# Adafruit_Hallowing_M4.net
KiCad netlist of a schematic drawn in EAGLE
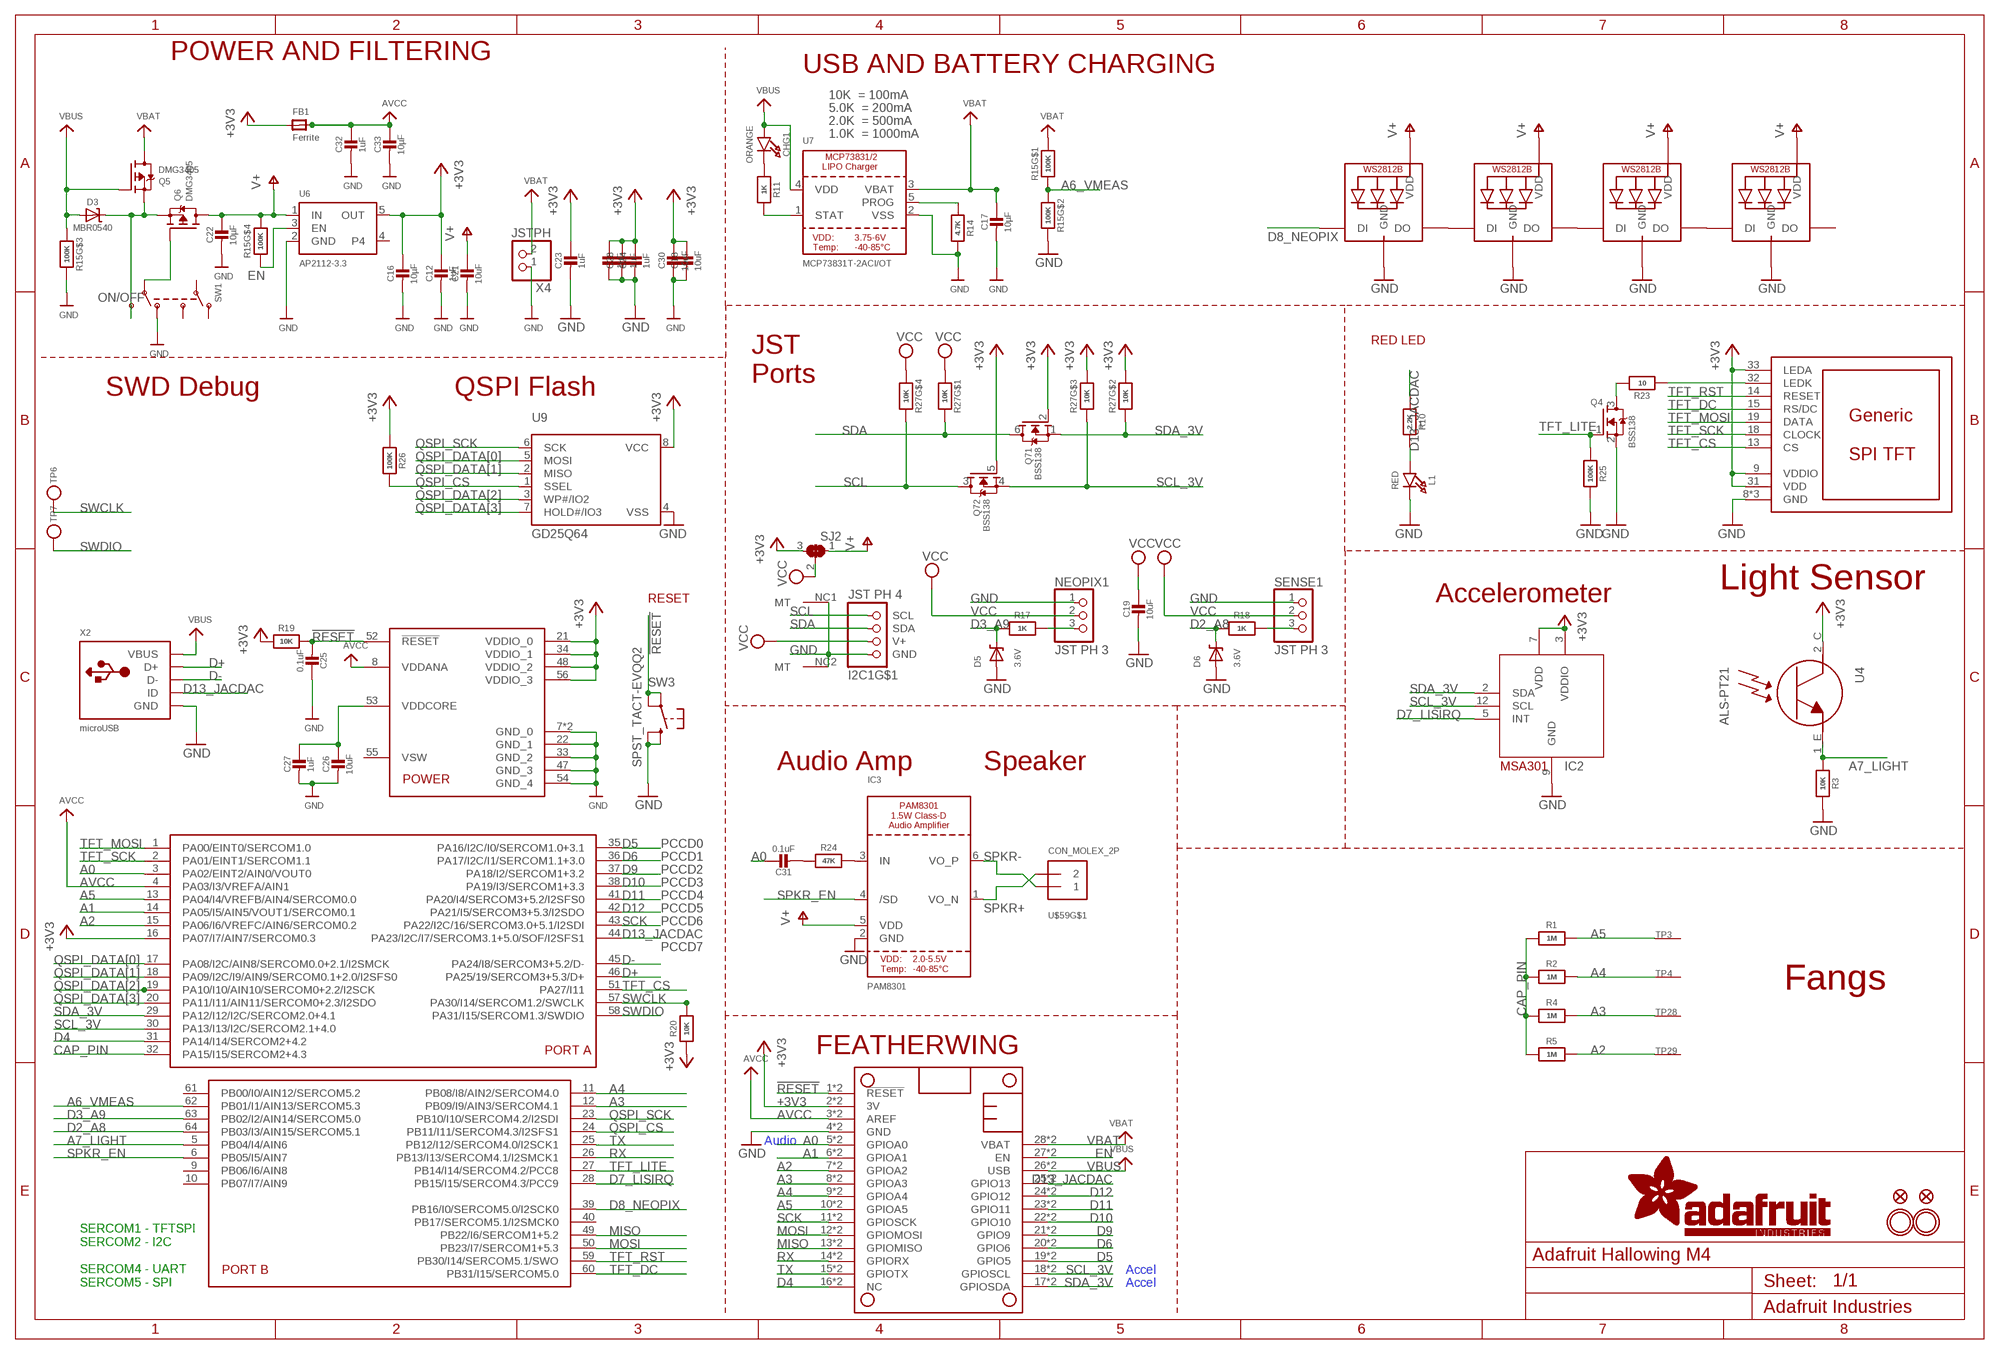
[diagram p0: schematic, sheet 1]

(export (version "E")
  (design (tool "Eeschema 10.0.6"))
  (components
    (comp (ref "C12")
      (value "1uF")
      (footprint "eagle-import:0603-NO")
      (libsource (lib "eagle-import") (part "CAP_CERAMIC0603_NO"))
    )
    (comp (ref "C16")
      (value "10µF")
      (footprint "eagle-import:0805-NO")
      (fields (field (name "REV") "C"))
      (libsource (lib "eagle-import") (part "CAP_CERAMIC0805-NOOUTLINE"))
    )
    (comp (ref "C17")
      (value "10µF")
      (footprint "eagle-import:0805-NO")
      (libsource (lib "eagle-import") (part "CAP_CERAMIC0805-NOOUTLINE"))
    )
    (comp (ref "C18")
      (value "10uF")
      (footprint "eagle-import:0805-NO")
      (libsource (lib "eagle-import") (part "CAP_CERAMIC0805-NOOUTLINE"))
    )
    (comp (ref "C19")
      (value "10uF")
      (footprint "eagle-import:0805-NO")
      (libsource (lib "eagle-import") (part "CAP_CERAMIC0805-NOOUTLINE"))
    )
    (comp (ref "C21")
      (value "10uF")
      (footprint "eagle-import:0805-NO")
      (libsource (lib "eagle-import") (part "CAP_CERAMIC0805-NOOUTLINE"))
    )
    (comp (ref "C22")
      (value "10µF")
      (footprint "eagle-import:0805-NO")
      (libsource (lib "eagle-import") (part "CAP_CERAMIC0805-NOOUTLINE"))
    )
    (comp (ref "C23")
      (value "1uF")
      (footprint "eagle-import:0603-NO")
      (libsource (lib "eagle-import") (part "CAP_CERAMIC0603_NO"))
    )
    (comp (ref "C24")
      (value "1uF")
      (footprint "eagle-import:0603-NO")
      (libsource (lib "eagle-import") (part "CAP_CERAMIC0603_NO"))
    )
    (comp (ref "C25")
      (value "0.1uF")
      (footprint "eagle-import:0603-NO")
      (libsource (lib "eagle-import") (part "CAP_CERAMIC0603_NO"))
    )
    (comp (ref "C26")
      (value "10uF")
      (footprint "eagle-import:0805-NO")
      (libsource (lib "eagle-import") (part "CAP_CERAMIC0805-NOOUTLINE"))
    )
    (comp (ref "C27")
      (value "1uF")
      (footprint "eagle-import:0603-NO")
      (libsource (lib "eagle-import") (part "CAP_CERAMIC0603_NO"))
    )
    (comp (ref "C28")
      (value "1uF")
      (footprint "eagle-import:0603-NO")
      (libsource (lib "eagle-import") (part "CAP_CERAMIC0603_NO"))
    )
    (comp (ref "C29")
      (value "1uF")
      (footprint "eagle-import:0603-NO")
      (libsource (lib "eagle-import") (part "CAP_CERAMIC0603_NO"))
    )
    (comp (ref "C30")
      (value "10uF")
      (footprint "eagle-import:0805-NO")
      (libsource (lib "eagle-import") (part "CAP_CERAMIC0805-NOOUTLINE"))
    )
    (comp (ref "C31")
      (value "0.1uF")
      (footprint "eagle-import:0603-NO")
      (libsource (lib "eagle-import") (part "CAP_CERAMIC0603_NO"))
    )
    (comp (ref "C32")
      (value "1uF")
      (footprint "eagle-import:0603-NO")
      (libsource (lib "eagle-import") (part "CAP_CERAMIC0603_NO"))
    )
    (comp (ref "C33")
      (value "10µF")
      (footprint "eagle-import:0805-NO")
      (libsource (lib "eagle-import") (part "CAP_CERAMIC0805-NOOUTLINE"))
    )
    (comp (ref "CHG1")
      (value "ORANGE")
      (footprint "eagle-import:CHIPLED_0805_NOOUTLINE")
      (libsource (lib "eagle-import") (part "LED0805_NOOUTLINE"))
    )
    (comp (ref "D3")
      (value "MBR0540")
      (footprint "eagle-import:SOD-123")
      (libsource (lib "eagle-import") (part "DIODE-SCHOTTKYSOD-123"))
    )
    (comp (ref "D5")
      (value "3.6V")
      (footprint "eagle-import:SOD-323")
      (libsource (lib "eagle-import") (part "DIODE-ZENERSOD323"))
    )
    (comp (ref "D6")
      (value "3.6V")
      (footprint "eagle-import:SOD-323")
      (libsource (lib "eagle-import") (part "DIODE-ZENERSOD323"))
    )
    (comp (ref "FB1")
      (value "Ferrite")
      (footprint "eagle-import:0805-NO")
      (libsource (lib "eagle-import") (part "FERRITE-0805NO"))
    )
    (comp (ref "I2C1")
      (value "JST PH 4")
      (footprint "eagle-import:JSTPH4")
      (libsource (lib "eagle-import") (part "STEMMA_I2C_RASMT"))
    )
    (comp (ref "IC2")
      (value "MSA301")
      (footprint "eagle-import:LGA12_2X2MM")
      (libsource (lib "eagle-import") (part "MSA301"))
    )
    (comp (ref "IC3")
      (value "PAM8301")
      (footprint "eagle-import:SOT23-6")
      (libsource (lib "eagle-import") (part "PAM8301"))
    )
    (comp (ref "L1")
      (value "RED")
      (footprint "eagle-import:CHIPLED_0805_NOOUTLINE")
      (libsource (lib "eagle-import") (part "LED0805_NOOUTLINE"))
    )
    (comp (ref "LED1")
      (value "WS2812B_4020")
      (footprint "eagle-import:WS2812B_4020")
      (libsource (lib "eagle-import") (part "WS2812B_4020"))
    )
    (comp (ref "LED2")
      (value "WS2812B_4020")
      (footprint "eagle-import:WS2812B_4020")
      (libsource (lib "eagle-import") (part "WS2812B_4020"))
    )
    (comp (ref "LED3")
      (value "WS2812B_4020")
      (footprint "eagle-import:WS2812B_4020")
      (libsource (lib "eagle-import") (part "WS2812B_4020"))
    )
    (comp (ref "LED4")
      (value "WS2812B_4020")
      (footprint "eagle-import:WS2812B_4020")
      (libsource (lib "eagle-import") (part "WS2812B_4020"))
    )
    (comp (ref "MS2")
      (value "FEATHERWING_SMTDUALNOHOLES")
      (footprint "eagle-import:FEATHERWING_SMT_NOHOLES")
      (libsource (lib "eagle-import") (part "FEATHERWING_SMTDUALNOHOLES"))
    )
    (comp (ref "NEOPIX1")
      (value "JST PH 3")
      (footprint "eagle-import:JSTPH3")
      (libsource (lib "eagle-import") (part "CON_JST_PH_3PIN"))
    )
    (comp (ref "Q4")
      (value "BSS138")
      (footprint "eagle-import:SOT23-WIDE")
      (libsource (lib "eagle-import") (part "MOSFET-NWIDE"))
    )
    (comp (ref "Q5")
      (value "DMG3405")
      (footprint "eagle-import:SOT23-R")
      (libsource (lib "eagle-import") (part "MOSFET-P"))
    )
    (comp (ref "Q6")
      (value "DMG3405")
      (footprint "eagle-import:SOT23-R")
      (libsource (lib "eagle-import") (part "MOSFET-P"))
    )
    (comp (ref "Q7")
      (value "BSS138")
      (footprint "eagle-import:SOT363")
      (libsource (lib "eagle-import") (part "MOSFET-N_DUAL"))
    )
    (comp (ref "R1")
      (value "1M")
      (footprint "eagle-import:0603-NO")
      (libsource (lib "eagle-import") (part "RESISTOR_0603_NOOUT"))
    )
    (comp (ref "R2")
      (value "1M")
      (footprint "eagle-import:0603-NO")
      (libsource (lib "eagle-import") (part "RESISTOR_0603_NOOUT"))
    )
    (comp (ref "R3")
      (value "10K")
      (footprint "eagle-import:0603-NO")
      (libsource (lib "eagle-import") (part "RESISTOR_0603_NOOUT"))
    )
    (comp (ref "R4")
      (value "1M")
      (footprint "eagle-import:0603-NO")
      (libsource (lib "eagle-import") (part "RESISTOR_0603_NOOUT"))
    )
    (comp (ref "R5")
      (value "1M")
      (footprint "eagle-import:0603-NO")
      (libsource (lib "eagle-import") (part "RESISTOR_0603_NOOUT"))
    )
    (comp (ref "R10")
      (value "2.2K")
      (footprint "eagle-import:0603-NO")
      (libsource (lib "eagle-import") (part "RESISTOR_0603_NOOUT"))
    )
    (comp (ref "R11")
      (value "1K")
      (footprint "eagle-import:0603-NO")
      (libsource (lib "eagle-import") (part "RESISTOR_0603_NOOUT"))
    )
    (comp (ref "R14")
      (value "4.7K")
      (footprint "eagle-import:0603-NO")
      (libsource (lib "eagle-import") (part "RESISTOR_0603_NOOUT"))
    )
    (comp (ref "R15")
      (value "100K")
      (footprint "eagle-import:RESPACK_4X0603")
      (libsource (lib "eagle-import") (part "RESISTOR_4PACK"))
    )
    (comp (ref "R17")
      (value "1K")
      (footprint "eagle-import:0603-NO")
      (libsource (lib "eagle-import") (part "RESISTOR_0603_NOOUT"))
    )
    (comp (ref "R18")
      (value "1K")
      (footprint "eagle-import:0603-NO")
      (libsource (lib "eagle-import") (part "RESISTOR_0603_NOOUT"))
    )
    (comp (ref "R19")
      (value "10K")
      (footprint "eagle-import:0603-NO")
      (libsource (lib "eagle-import") (part "RESISTOR_0603_NOOUT"))
    )
    (comp (ref "R20")
      (value "10K")
      (footprint "eagle-import:0603-NO")
      (libsource (lib "eagle-import") (part "RESISTOR_0603_NOOUT"))
    )
    (comp (ref "R23")
      (value "10")
      (footprint "eagle-import:0603-NO")
      (libsource (lib "eagle-import") (part "RESISTOR_0603_NOOUT"))
    )
    (comp (ref "R24")
      (value "47K")
      (footprint "eagle-import:0603-NO")
      (libsource (lib "eagle-import") (part "RESISTOR_0603_NOOUT"))
    )
    (comp (ref "R25")
      (value "100K")
      (footprint "eagle-import:0603-NO")
      (libsource (lib "eagle-import") (part "RESISTOR_0603_NOOUT"))
    )
    (comp (ref "R26")
      (value "100K")
      (footprint "eagle-import:0603-NO")
      (libsource (lib "eagle-import") (part "RESISTOR_0603_NOOUT"))
    )
    (comp (ref "R27")
      (value "10K")
      (footprint "eagle-import:RESPACK_4X0603")
      (libsource (lib "eagle-import") (part "RESISTOR_4PACK"))
    )
    (comp (ref "SENSE1")
      (value "JST PH 3")
      (footprint "eagle-import:JSTPH3")
      (libsource (lib "eagle-import") (part "CON_JST_PH_3PIN"))
    )
    (comp (ref "SJ2")
      (value "SOLDERJUMPER_2WAY")
      (footprint "eagle-import:SOLDERJUMPER_2WAY_OPEN_NOPASTE")
      (libsource (lib "eagle-import") (part "SOLDERJUMPER_2WAY"))
    )
    (comp (ref "SW1")
      (value "SWITCH_DPDTEG1390")
      (footprint "eagle-import:EG1390")
      (libsource (lib "eagle-import") (part "SWITCH_DPDTEG1390"))
    )
    (comp (ref "SW3")
      (value "SPST_TACT-EVQQ2")
      (footprint "eagle-import:BTN_KMR2_4.6X2.8")
      (libsource (lib "eagle-import") (part "SWITCH_TACT_SMT4.6X2.8"))
    )
    (comp (ref "TFT1")
      (value "DISP_LCD_GENERIC_SPITFT_VDDIO_1.54_240X240_HANDSOLDER")
      (footprint "eagle-import:TFT_1.54IN_240X240_HANDSOLDER")
      (libsource (lib "eagle-import") (part "DISP_LCD_GENERIC_SPITFT_VDDIO_1.54_240X240_HANDSOLDER"))
    )
    (comp (ref "TP3")
      (value "SEWTAP_ALLILONG")
      (footprint "eagle-import:PCB_ALLI_LONG")
      (libsource (lib "eagle-import") (part "SEWTAP_ALLILONG"))
    )
    (comp (ref "TP4")
      (value "SEWTAPPCB_ALLIGATOR")
      (footprint "eagle-import:PCB_ALLI")
      (libsource (lib "eagle-import") (part "SEWTAPPCB_ALLIGATOR"))
    )
    (comp (ref "TP6")
      (value "TESTPOINTROUND1.5MM")
      (footprint "eagle-import:TESTPOINT_ROUND_1.5MM")
      (libsource (lib "eagle-import") (part "TESTPOINTROUND1.5MM"))
    )
    (comp (ref "TP7")
      (value "TESTPOINTROUND1.5MM")
      (footprint "eagle-import:TESTPOINT_ROUND_1.5MM")
      (libsource (lib "eagle-import") (part "TESTPOINTROUND1.5MM"))
    )
    (comp (ref "TP28")
      (value "SEWTAPPCB_ALLIGATOR")
      (footprint "eagle-import:PCB_ALLI")
      (libsource (lib "eagle-import") (part "SEWTAPPCB_ALLIGATOR"))
    )
    (comp (ref "TP29")
      (value "SEWTAP_ALLILONG")
      (footprint "eagle-import:PCB_ALLI_LONG")
      (libsource (lib "eagle-import") (part "SEWTAP_ALLILONG"))
    )
    (comp (ref "U$31")
      (value "MOUNTINGHOLE2.5")
      (footprint "eagle-import:MOUNTINGHOLE_2.5_PLATED")
      (libsource (lib "eagle-import") (part "MOUNTINGHOLE2.5"))
    )
    (comp (ref "U$32")
      (value "MOUNTINGHOLE2.5")
      (footprint "eagle-import:MOUNTINGHOLE_2.5_PLATED")
      (libsource (lib "eagle-import") (part "MOUNTINGHOLE2.5"))
    )
    (comp (ref "U$34")
      (value "FIDUCIAL_1MM")
      (footprint "eagle-import:FIDUCIAL_1MM")
      (libsource (lib "eagle-import") (part "FIDUCIAL_1MM"))
    )
    (comp (ref "U$35")
      (value "FIDUCIAL_1MM")
      (footprint "eagle-import:FIDUCIAL_1MM")
      (libsource (lib "eagle-import") (part "FIDUCIAL_1MM"))
    )
    (comp (ref "U$59")
      (value "CON_MOLEX_2P")
      (footprint "eagle-import:53398-0271")
      (libsource (lib "eagle-import") (part "CON_MOLEX_2P"))
    )
    (comp (ref "U$63")
      (value "ATSAMD51J19")
      (footprint "eagle-import:PQFN64-1")
      (libsource (lib "eagle-import") (part "ATSAMD51J"))
    )
    (comp (ref "U4")
      (value "ALS-PT21")
      (footprint "eagle-import:ALS-PT26-21C")
      (libsource (lib "eagle-import") (part "PHOTOTRANSISTOR_PT26-21C"))
    )
    (comp (ref "U6")
      (value "AP2112-3.3")
      (footprint "eagle-import:SOT23-5")
      (libsource (lib "eagle-import") (part "VREG_SOT23-5"))
    )
    (comp (ref "U7")
      (value "MCP73831T-2ACI/OT")
      (footprint "eagle-import:SOT23-5")
      (libsource (lib "eagle-import") (part "MCP73831/2"))
    )
    (comp (ref "U9")
      (value "GD25Q64")
      (footprint "eagle-import:SOIC8_208MIL")
      (libsource (lib "eagle-import") (part "SPIFLASH_8PIN208MIL"))
    )
    (comp (ref "X2")
      (value "microUSB")
      (footprint "eagle-import:4UCONN_20329_V2")
      (libsource (lib "eagle-import") (part "USB_MICRO_20329_V2"))
    )
    (comp (ref "X4")
      (value "JSTPH")
      (footprint "eagle-import:JSTPH2")
      (libsource (lib "eagle-import") (part "CON_JST_PH_2PIN"))
    )
  )
  (nets
    (net (code "1") (name "+3V3") (class "Default")
      (node (ref "C12") (pin "1") (pinfunction "1_1") (pintype "passive"))
      (node (ref "C16") (pin "1") (pinfunction "1_1") (pintype "passive"))
      (node (ref "C18") (pin "1") (pinfunction "1_1") (pintype "passive"))
      (node (ref "C23") (pin "1") (pinfunction "1_1") (pintype "passive"))
      (node (ref "C24") (pin "1") (pinfunction "1_1") (pintype "passive"))
      (node (ref "C28") (pin "1") (pinfunction "1_1") (pintype "passive"))
      (node (ref "C29") (pin "1") (pinfunction "1_1") (pintype "passive"))
      (node (ref "C30") (pin "1") (pinfunction "1_1") (pintype "passive"))
      (node (ref "FB1") (pin "1") (pinfunction "P$1_1") (pintype "passive"))
      (node (ref "IC2") (pin "3") (pinfunction "VDDIO_3") (pintype "power_in"))
      (node (ref "IC2") (pin "7") (pinfunction "VDD_7") (pintype "power_in"))
      (node (ref "MS2") (pin "2") (pinfunction "3V_2") (pintype "power_in"))
      (node (ref "MS2") (pin "2B") (pinfunction "3V_2B") (pintype "power_in"))
      (node (ref "Q7") (pin "2") (pinfunction "G_2") (pintype "bidirectional"))
      (node (ref "Q7") (pin "5") (pinfunction "G_5") (pintype "bidirectional"))
      (node (ref "R19") (pin "1") (pinfunction "1_1") (pintype "passive"))
      (node (ref "R20") (pin "1") (pinfunction "1_1") (pintype "passive"))
      (node (ref "R26") (pin "1") (pinfunction "1_1") (pintype "passive"))
      (node (ref "R27") (pin "2") (pinfunction "1_2") (pintype "passive"))
      (node (ref "R27") (pin "3") (pinfunction "1_3") (pintype "passive"))
      (node (ref "SJ2") (pin "3") (pinfunction "3_3") (pintype "passive"))
      (node (ref "TFT1") (pin "31") (pinfunction "VDD_31") (pintype "power_in"))
      (node (ref "TFT1") (pin "33") (pinfunction "LEDA_33") (pintype "input"))
      (node (ref "TFT1") (pin "9") (pinfunction "VDDIO_9") (pintype "power_in"))
      (node (ref "U$63") (pin "16") (pinfunction "PA07/I7/AIN7/SERCOM0.3_16") (pintype "bidirectional"))
      (node (ref "U$63") (pin "21") (pinfunction "VDDIO_0_21") (pintype "bidirectional"))
      (node (ref "U$63") (pin "34") (pinfunction "VDDIO_1_34") (pintype "bidirectional"))
      (node (ref "U$63") (pin "48") (pinfunction "VDDIO_2_48") (pintype "bidirectional"))
      (node (ref "U$63") (pin "56") (pinfunction "VDDIO_3_56") (pintype "bidirectional"))
      (node (ref "U4") (pin "2_C") (pinfunction "C_2_C") (pintype "bidirectional"))
      (node (ref "U6") (pin "5") (pinfunction "OUT_5") (pintype "power_in"))
      (node (ref "U9") (pin "8") (pinfunction "VCC_8") (pintype "bidirectional"))
    )
    (net (code "2") (name "/A0") (class "Default")
      (node (ref "C31") (pin "1") (pinfunction "1_1") (pintype "passive"))
      (node (ref "MS2") (pin "5") (pinfunction "GPIOA0_5") (pintype "bidirectional"))
      (node (ref "MS2") (pin "5B") (pinfunction "GPIOA0_5B") (pintype "bidirectional"))
      (node (ref "U$63") (pin "3") (pinfunction "PA02/EINT2/AIN0/VOUT0_3") (pintype "bidirectional"))
    )
    (net (code "3") (name "/A1") (class "Default")
      (node (ref "MS2") (pin "6") (pinfunction "GPIOA1_6") (pintype "bidirectional"))
      (node (ref "MS2") (pin "6B") (pinfunction "GPIOA1_6B") (pintype "bidirectional"))
      (node (ref "U$63") (pin "14") (pinfunction "PA05/I5/AIN5/VOUT1/SERCOM0.1_14") (pintype "bidirectional"))
    )
    (net (code "4") (name "/A2") (class "Default")
      (node (ref "MS2") (pin "7") (pinfunction "GPIOA2_7") (pintype "bidirectional"))
      (node (ref "MS2") (pin "7B") (pinfunction "GPIOA2_7B") (pintype "bidirectional"))
      (node (ref "R5") (pin "1") (pinfunction "1_1") (pintype "passive"))
      (node (ref "TP29") (pin "P$1") (pinfunction "SEW_P$1") (pintype "bidirectional"))
      (node (ref "U$63") (pin "15") (pinfunction "PA06/I6/VREFC/AIN6/SERCOM0.2_15") (pintype "bidirectional"))
    )
    (net (code "5") (name "/A3") (class "Default")
      (node (ref "MS2") (pin "8") (pinfunction "GPIOA3_8") (pintype "bidirectional"))
      (node (ref "MS2") (pin "8B") (pinfunction "GPIOA3_8B") (pintype "bidirectional"))
      (node (ref "R4") (pin "1") (pinfunction "1_1") (pintype "passive"))
      (node (ref "TP28") (pin "P$1") (pinfunction "SEW_P$1") (pintype "bidirectional"))
      (node (ref "U$63") (pin "12") (pinfunction "PB09/I9/AIN3/SERCOM4.1_12") (pintype "bidirectional"))
    )
    (net (code "6") (name "/A4") (class "Default")
      (node (ref "MS2") (pin "9") (pinfunction "GPIOA4_9") (pintype "bidirectional"))
      (node (ref "MS2") (pin "9B") (pinfunction "GPIOA4_9B") (pintype "bidirectional"))
      (node (ref "R2") (pin "1") (pinfunction "1_1") (pintype "passive"))
      (node (ref "TP4") (pin "P$1") (pinfunction "SEW_P$1") (pintype "bidirectional"))
      (node (ref "U$63") (pin "11") (pinfunction "PB08/I8/AIN2/SERCOM4.0_11") (pintype "bidirectional"))
    )
    (net (code "7") (name "/A5") (class "Default")
      (node (ref "MS2") (pin "10") (pinfunction "GPIOA5_10") (pintype "bidirectional"))
      (node (ref "MS2") (pin "10B") (pinfunction "GPIOA5_10B") (pintype "bidirectional"))
      (node (ref "R1") (pin "1") (pinfunction "1_1") (pintype "passive"))
      (node (ref "TP3") (pin "P$1") (pinfunction "SEW_P$1") (pintype "bidirectional"))
      (node (ref "U$63") (pin "13") (pinfunction "PA04/I4/VREFB/AIN4/SERCOM0.0_13") (pintype "bidirectional"))
    )
    (net (code "8") (name "/A6_VMEAS") (class "Default")
      (node (ref "R15") (pin "1") (pinfunction "1_1") (pintype "passive"))
      (node (ref "R15") (pin "2") (pinfunction "1_2") (pintype "passive"))
      (node (ref "U$63") (pin "62") (pinfunction "PB01/I1/AIN13/SERCOM5.3_62") (pintype "bidirectional"))
    )
    (net (code "9") (name "/A7_LIGHT") (class "Default")
      (node (ref "R3") (pin "2") (pinfunction "2_2") (pintype "passive"))
      (node (ref "U$63") (pin "5") (pinfunction "PB04/I4/AIN6_5") (pintype "bidirectional"))
      (node (ref "U4") (pin "1_E") (pinfunction "E_1_E") (pintype "bidirectional"))
    )
    (net (code "10") (name "/CAP_PIN") (class "Default")
      (node (ref "R1") (pin "2") (pinfunction "2_2") (pintype "passive"))
      (node (ref "R2") (pin "2") (pinfunction "2_2") (pintype "passive"))
      (node (ref "R4") (pin "2") (pinfunction "2_2") (pintype "passive"))
      (node (ref "R5") (pin "2") (pinfunction "2_2") (pintype "passive"))
      (node (ref "U$63") (pin "32") (pinfunction "PA15/I15/SERCOM2+4.3_32") (pintype "bidirectional"))
    )
    (net (code "11") (name "/D+") (class "Default")
      (node (ref "U$63") (pin "46") (pinfunction "PA25/19/SERCOM3+5.3/D+_46") (pintype "bidirectional"))
      (node (ref "X2") (pin "D+") (pinfunction "D+_D+") (pintype "bidirectional"))
    )
    (net (code "12") (name "/D-") (class "Default")
      (node (ref "U$63") (pin "45") (pinfunction "PA24/I8/SERCOM3+5.2/D-_45") (pintype "bidirectional"))
      (node (ref "X2") (pin "D-") (pinfunction "D-_D-") (pintype "bidirectional"))
    )
    (net (code "13") (name "/D2_A8") (class "Default")
      (node (ref "D6") (pin "C") (pinfunction "C_C") (pintype "passive"))
      (node (ref "R18") (pin "2") (pinfunction "2_2") (pintype "passive"))
      (node (ref "U$63") (pin "64") (pinfunction "PB03/I3/AIN15/SERCOM5.1_64") (pintype "bidirectional"))
    )
    (net (code "14") (name "/D3_A9") (class "Default")
      (node (ref "D5") (pin "C") (pinfunction "C_C") (pintype "passive"))
      (node (ref "R17") (pin "2") (pinfunction "2_2") (pintype "passive"))
      (node (ref "U$63") (pin "63") (pinfunction "PB02/I2/AIN14/SERCOM5.0_63") (pintype "bidirectional"))
    )
    (net (code "15") (name "/D4") (class "Default")
      (node (ref "MS2") (pin "16") (pinfunction "NC_16") (pintype "passive"))
      (node (ref "MS2") (pin "16B") (pinfunction "NC_16B") (pintype "passive"))
      (node (ref "U$63") (pin "31") (pinfunction "PA14/I14/SERCOM2+4.2_31") (pintype "bidirectional"))
    )
    (net (code "16") (name "/D5") (class "Default")
      (node (ref "MS2") (pin "19") (pinfunction "GPIO5_19") (pintype "bidirectional"))
      (node (ref "MS2") (pin "19B") (pinfunction "GPIO5_19B") (pintype "bidirectional"))
      (node (ref "U$63") (pin "35") (pinfunction "PA16/I2C/I0/SERCOM1.0+3.1_35") (pintype "bidirectional"))
    )
    (net (code "17") (name "/D6") (class "Default")
      (node (ref "MS2") (pin "20") (pinfunction "GPIO6_20") (pintype "bidirectional"))
      (node (ref "MS2") (pin "20B") (pinfunction "GPIO6_20B") (pintype "bidirectional"))
      (node (ref "U$63") (pin "36") (pinfunction "PA17/I2C/I1/SERCOM1.1+3.0_36") (pintype "bidirectional"))
    )
    (net (code "18") (name "/D7_LISIRQ") (class "Default")
      (node (ref "IC2") (pin "5") (pinfunction "INT_5") (pintype "output"))
      (node (ref "U$63") (pin "28") (pinfunction "PB15/I15/SERCOM4.3/PCC9_28") (pintype "bidirectional"))
    )
    (net (code "19") (name "/D8_NEOPIX") (class "Default")
      (node (ref "LED2") (pin "1") (pinfunction "DI_1") (pintype "input"))
      (node (ref "U$63") (pin "39") (pinfunction "PB16/I0/SERCOM5.0/I2SCK0_39") (pintype "bidirectional"))
    )
    (net (code "20") (name "/D9") (class "Default")
      (node (ref "MS2") (pin "21") (pinfunction "GPIO9_21") (pintype "bidirectional"))
      (node (ref "MS2") (pin "21B") (pinfunction "GPIO9_21B") (pintype "bidirectional"))
      (node (ref "U$63") (pin "37") (pinfunction "PA18/I2/SERCOM1+3.2_37") (pintype "bidirectional"))
    )
    (net (code "21") (name "/D10") (class "Default")
      (node (ref "MS2") (pin "22") (pinfunction "GPIO10_22") (pintype "bidirectional"))
      (node (ref "MS2") (pin "22B") (pinfunction "GPIO10_22B") (pintype "bidirectional"))
      (node (ref "U$63") (pin "38") (pinfunction "PA19/I3/SERCOM1+3.3_38") (pintype "bidirectional"))
    )
    (net (code "22") (name "/D11") (class "Default")
      (node (ref "MS2") (pin "23") (pinfunction "GPIO11_23") (pintype "bidirectional"))
      (node (ref "MS2") (pin "23B") (pinfunction "GPIO11_23B") (pintype "bidirectional"))
      (node (ref "U$63") (pin "41") (pinfunction "PA20/I4/SERCOM3+5.2/I2SFS0_41") (pintype "bidirectional"))
    )
    (net (code "23") (name "/D12") (class "Default")
      (node (ref "MS2") (pin "24") (pinfunction "GPIO12_24") (pintype "bidirectional"))
      (node (ref "MS2") (pin "24B") (pinfunction "GPIO12_24B") (pintype "bidirectional"))
      (node (ref "U$63") (pin "42") (pinfunction "PA21/I5/SERCOM3+5.3/I2SDO_42") (pintype "bidirectional"))
    )
    (net (code "24") (name "/D13_JACDAC") (class "Default")
      (node (ref "MS2") (pin "25") (pinfunction "GPIO13_25") (pintype "bidirectional"))
      (node (ref "MS2") (pin "25B") (pinfunction "GPIO13_25B") (pintype "bidirectional"))
      (node (ref "R10") (pin "1") (pinfunction "1_1") (pintype "passive"))
      (node (ref "U$63") (pin "44") (pinfunction "PA23/I2C/I7/SERCOM3.1+5.0/SOF/I2SFS1_44") (pintype "bidirectional"))
      (node (ref "X2") (pin "ID") (pinfunction "ID_ID") (pintype "bidirectional"))
    )
    (net (code "25") (name "/EN") (class "Default")
      (node (ref "MS2") (pin "27") (pinfunction "EN_27") (pintype "passive"))
      (node (ref "MS2") (pin "27B") (pinfunction "EN_27B") (pintype "passive"))
      (node (ref "R15") (pin "4") (pinfunction "1_4") (pintype "passive"))
      (node (ref "U6") (pin "3") (pinfunction "EN_3") (pintype "input"))
    )
    (net (code "26") (name "/MISO") (class "Default")
      (node (ref "MS2") (pin "13") (pinfunction "GPIOMISO_13") (pintype "bidirectional"))
      (node (ref "MS2") (pin "13B") (pinfunction "GPIOMISO_13B") (pintype "bidirectional"))
      (node (ref "U$63") (pin "49") (pinfunction "PB22/I6/SERCOM1+5.2_49") (pintype "bidirectional"))
    )
    (net (code "27") (name "/MOSI") (class "Default")
      (node (ref "MS2") (pin "12") (pinfunction "GPIOMOSI_12") (pintype "bidirectional"))
      (node (ref "MS2") (pin "12B") (pinfunction "GPIOMOSI_12B") (pintype "bidirectional"))
      (node (ref "U$63") (pin "50") (pinfunction "PB23/I7/SERCOM1+5.3_50") (pintype "bidirectional"))
    )
    (net (code "28") (name "/ON{slash}OFF") (class "Default")
      (node (ref "Q6") (pin "1") (pinfunction "G_1") (pintype "passive"))
      (node (ref "SW1") (pin "P2") (pinfunction "P2_P2") (pintype "passive"))
    )
    (net (code "29") (name "/QSPI_CS") (class "Default")
      (node (ref "R26") (pin "2") (pinfunction "2_2") (pintype "passive"))
      (node (ref "U$63") (pin "24") (pinfunction "PB11/I11/SERCOM4.3/I2SFS1_24") (pintype "bidirectional"))
      (node (ref "U9") (pin "1") (pinfunction "SSEL_1") (pintype "bidirectional"))
    )
    (net (code "30") (name "/QSPI_DATA[0]") (class "Default")
      (node (ref "U$63") (pin "17") (pinfunction "PA08/I2C/AIN8/SERCOM0.0+2.1/I2SMCK_17") (pintype "bidirectional"))
      (node (ref "U9") (pin "5") (pinfunction "MOSI_5") (pintype "bidirectional"))
    )
    (net (code "31") (name "/QSPI_DATA[1]") (class "Default")
      (node (ref "U$63") (pin "18") (pinfunction "PA09/I2C/I9/AIN9/SERCOM0.1+2.0/I2SFS0_18") (pintype "bidirectional"))
      (node (ref "U9") (pin "2") (pinfunction "MISO_2") (pintype "bidirectional"))
    )
    (net (code "32") (name "/QSPI_DATA[2]") (class "Default")
      (node (ref "U$63") (pin "19") (pinfunction "PA10/I10/AIN10/SERCOM0+2.2/I2SCK_19") (pintype "bidirectional"))
      (node (ref "U9") (pin "3") (pinfunction "WP#/IO2_3") (pintype "bidirectional"))
    )
    (net (code "33") (name "/QSPI_DATA[3]") (class "Default")
      (node (ref "U$63") (pin "20") (pinfunction "PA11/I11/AIN11/SERCOM0+2.3/I2SDO_20") (pintype "bidirectional"))
      (node (ref "U9") (pin "7") (pinfunction "HOLD#/IO3_7") (pintype "bidirectional"))
    )
    (net (code "34") (name "/QSPI_SCK") (class "Default")
      (node (ref "U$63") (pin "23") (pinfunction "PB10/I10/SERCOM4.2/I2SDI_23") (pintype "bidirectional"))
      (node (ref "U9") (pin "6") (pinfunction "SCK_6") (pintype "bidirectional"))
    )
    (net (code "35") (name "/RX") (class "Default")
      (node (ref "MS2") (pin "14") (pinfunction "GPIORX_14") (pintype "bidirectional"))
      (node (ref "MS2") (pin "14B") (pinfunction "GPIORX_14B") (pintype "bidirectional"))
      (node (ref "U$63") (pin "26") (pinfunction "PB13/I13/SERCOM4.1/I2SMCK1_26") (pintype "bidirectional"))
    )
    (net (code "36") (name "/SCK") (class "Default")
      (node (ref "MS2") (pin "11") (pinfunction "GPIOSCK_11") (pintype "bidirectional"))
      (node (ref "MS2") (pin "11B") (pinfunction "GPIOSCK_11B") (pintype "bidirectional"))
      (node (ref "U$63") (pin "43") (pinfunction "PA22/I2C/16/SERCOM3.0+5.1/I2SDI_43") (pintype "bidirectional"))
    )
    (net (code "37") (name "/SCL") (class "Default")
      (node (ref "I2C1") (pin "4") (pinfunction "SCL_4") (pintype "passive"))
      (node (ref "Q7") (pin "3") (pinfunction "D_3") (pintype "bidirectional"))
      (node (ref "R27") (pin "5") (pinfunction "2_5") (pintype "passive"))
    )
    (net (code "38") (name "/SCL_3V") (class "Default")
      (node (ref "IC2") (pin "12") (pinfunction "SCL_12") (pintype "bidirectional"))
      (node (ref "MS2") (pin "18") (pinfunction "GPIOSCL_18") (pintype "bidirectional"))
      (node (ref "MS2") (pin "18B") (pinfunction "GPIOSCL_18B") (pintype "bidirectional"))
      (node (ref "Q7") (pin "4") (pinfunction "S_4") (pintype "bidirectional"))
      (node (ref "R27") (pin "6") (pinfunction "2_6") (pintype "passive"))
      (node (ref "U$63") (pin "30") (pinfunction "PA13/I13/I2C/SERCOM2.1+4.0_30") (pintype "bidirectional"))
    )
    (net (code "39") (name "/SDA") (class "Default")
      (node (ref "I2C1") (pin "3") (pinfunction "SDA_3") (pintype "passive"))
      (node (ref "Q7") (pin "6") (pinfunction "D_6") (pintype "bidirectional"))
      (node (ref "R27") (pin "8") (pinfunction "2_8") (pintype "passive"))
    )
    (net (code "40") (name "/SDA_3V") (class "Default")
      (node (ref "IC2") (pin "2") (pinfunction "SDA_2") (pintype "bidirectional"))
      (node (ref "MS2") (pin "17") (pinfunction "GPIOSDA_17") (pintype "bidirectional"))
      (node (ref "MS2") (pin "17B") (pinfunction "GPIOSDA_17B") (pintype "bidirectional"))
      (node (ref "Q7") (pin "1") (pinfunction "S_1") (pintype "bidirectional"))
      (node (ref "R27") (pin "7") (pinfunction "2_7") (pintype "passive"))
      (node (ref "U$63") (pin "29") (pinfunction "PA12/I12/I2C/SERCOM2.0+4.1_29") (pintype "bidirectional"))
    )
    (net (code "41") (name "/SPKR+") (class "Default")
      (node (ref "IC3") (pin "1") (pinfunction "VO_N_1") (pintype "output"))
      (node (ref "U$59") (pin "2") (pinfunction "2_2") (pintype "passive"))
    )
    (net (code "42") (name "/SPKR-") (class "Default")
      (node (ref "IC3") (pin "6") (pinfunction "VO_P_6") (pintype "output"))
      (node (ref "U$59") (pin "1") (pinfunction "1_1") (pintype "passive"))
    )
    (net (code "43") (name "/SPKR_EN") (class "Default")
      (node (ref "IC3") (pin "4") (pinfunction "/SD_4") (pintype "input"))
      (node (ref "U$63") (pin "6") (pinfunction "PB05/I5/AIN7_6") (pintype "bidirectional"))
    )
    (net (code "44") (name "/SWCLK") (class "Default")
      (node (ref "R20") (pin "2") (pinfunction "2_2") (pintype "passive"))
      (node (ref "TP6") (pin "P$1") (pinfunction "P$1_P$1") (pintype "bidirectional"))
      (node (ref "U$63") (pin "57") (pinfunction "PA30/I14/SERCOM1.2/SWCLK_57") (pintype "bidirectional"))
    )
    (net (code "45") (name "/SWDIO") (class "Default")
      (node (ref "TP7") (pin "P$1") (pinfunction "P$1_P$1") (pintype "bidirectional"))
      (node (ref "U$63") (pin "58") (pinfunction "PA31/I15/SERCOM1.3/SWDIO_58") (pintype "bidirectional"))
    )
    (net (code "46") (name "/TFT_CS") (class "Default")
      (node (ref "TFT1") (pin "13") (pinfunction "CS_13") (pintype "input"))
      (node (ref "U$63") (pin "51") (pinfunction "PA27/I11_51") (pintype "bidirectional"))
    )
    (net (code "47") (name "/TFT_DC") (class "Default")
      (node (ref "TFT1") (pin "15") (pinfunction "RS/DC_15") (pintype "input"))
      (node (ref "U$63") (pin "60") (pinfunction "PB31/I15/SERCOM5.0_60") (pintype "bidirectional"))
    )
    (net (code "48") (name "/TFT_LITE") (class "Default")
      (node (ref "Q4") (pin "1") (pinfunction "G_1") (pintype "bidirectional"))
      (node (ref "R25") (pin "1") (pinfunction "1_1") (pintype "passive"))
      (node (ref "U$63") (pin "27") (pinfunction "PB14/I14/SERCOM4.2/PCC8_27") (pintype "bidirectional"))
    )
    (net (code "49") (name "/TFT_MOSI") (class "Default")
      (node (ref "TFT1") (pin "19") (pinfunction "DATA_19") (pintype "bidirectional"))
      (node (ref "U$63") (pin "1") (pinfunction "PA00/EINT0/SERCOM1.0_1") (pintype "bidirectional"))
    )
    (net (code "50") (name "/TFT_RST") (class "Default")
      (node (ref "TFT1") (pin "14") (pinfunction "RESET_14") (pintype "input"))
      (node (ref "U$63") (pin "59") (pinfunction "PB30/I14/SERCOM5.1/SWO_59") (pintype "bidirectional"))
    )
    (net (code "51") (name "/TFT_SCK") (class "Default")
      (node (ref "TFT1") (pin "18") (pinfunction "CLOCK_18") (pintype "input"))
      (node (ref "U$63") (pin "2") (pinfunction "PA01/EINT1/SERCOM1.1_2") (pintype "bidirectional"))
    )
    (net (code "52") (name "/TX") (class "Default")
      (node (ref "MS2") (pin "15") (pinfunction "GPIOTX_15") (pintype "bidirectional"))
      (node (ref "MS2") (pin "15B") (pinfunction "GPIOTX_15B") (pintype "bidirectional"))
      (node (ref "U$63") (pin "25") (pinfunction "PB12/I12/SERCOM4.0/I2SCK1_25") (pintype "bidirectional"))
    )
    (net (code "53") (name "/~{RESET}") (class "Default")
      (node (ref "C25") (pin "2") (pinfunction "2_2") (pintype "passive"))
      (node (ref "MS2") (pin "1") (pinfunction "~{RESET}_1") (pintype "input"))
      (node (ref "MS2") (pin "1B") (pinfunction "~{RESET}_1B") (pintype "input"))
      (node (ref "R19") (pin "2") (pinfunction "2_2") (pintype "passive"))
      (node (ref "SW3") (pin "A") (pinfunction "P_A") (pintype "passive"))
      (node (ref "SW3") (pin "A'") (pinfunction "P1_A'") (pintype "passive"))
      (node (ref "U$63") (pin "52") (pinfunction "~{RESET}_52") (pintype "bidirectional"))
    )
    (net (code "54") (name "AVCC") (class "Default")
      (node (ref "C32") (pin "1") (pinfunction "1_1") (pintype "passive"))
      (node (ref "C33") (pin "1") (pinfunction "1_1") (pintype "passive"))
      (node (ref "FB1") (pin "2") (pinfunction "P$2_2") (pintype "passive"))
      (node (ref "MS2") (pin "3") (pinfunction "AREF_3") (pintype "passive"))
      (node (ref "MS2") (pin "3B") (pinfunction "AREF_3B") (pintype "passive"))
      (node (ref "U$63") (pin "4") (pinfunction "PA03/I3/VREFA/AIN1_4") (pintype "bidirectional"))
      (node (ref "U$63") (pin "8") (pinfunction "VDDANA_8") (pintype "bidirectional"))
    )
    (net (code "55") (name "GND") (class "Default")
      (node (ref "C12") (pin "2") (pinfunction "2_2") (pintype "passive"))
      (node (ref "C16") (pin "2") (pinfunction "2_2") (pintype "passive"))
      (node (ref "C17") (pin "2") (pinfunction "2_2") (pintype "passive"))
      (node (ref "C18") (pin "2") (pinfunction "2_2") (pintype "passive"))
      (node (ref "C19") (pin "2") (pinfunction "2_2") (pintype "passive"))
      (node (ref "C21") (pin "2") (pinfunction "2_2") (pintype "passive"))
      (node (ref "C22") (pin "2") (pinfunction "2_2") (pintype "passive"))
      (node (ref "C23") (pin "2") (pinfunction "2_2") (pintype "passive"))
      (node (ref "C24") (pin "2") (pinfunction "2_2") (pintype "passive"))
      (node (ref "C25") (pin "1") (pinfunction "1_1") (pintype "passive"))
      (node (ref "C26") (pin "2") (pinfunction "2_2") (pintype "passive"))
      (node (ref "C27") (pin "2") (pinfunction "2_2") (pintype "passive"))
      (node (ref "C28") (pin "2") (pinfunction "2_2") (pintype "passive"))
      (node (ref "C29") (pin "2") (pinfunction "2_2") (pintype "passive"))
      (node (ref "C30") (pin "2") (pinfunction "2_2") (pintype "passive"))
      (node (ref "C32") (pin "2") (pinfunction "2_2") (pintype "passive"))
      (node (ref "C33") (pin "2") (pinfunction "2_2") (pintype "passive"))
      (node (ref "D5") (pin "A") (pinfunction "A_A") (pintype "passive"))
      (node (ref "D6") (pin "A") (pinfunction "A_A") (pintype "passive"))
      (node (ref "I2C1") (pin "1") (pinfunction "GND_1") (pintype "passive"))
      (node (ref "I2C1") (pin "NC1") (pinfunction "MT_NC1") (pintype "bidirectional"))
      (node (ref "I2C1") (pin "NC2") (pinfunction "MT_NC2") (pintype "bidirectional"))
      (node (ref "IC2") (pin "9") (pinfunction "GND_9") (pintype "power_in"))
      (node (ref "IC3") (pin "2") (pinfunction "GND_2") (pintype "power_in"))
      (node (ref "L1") (pin "C") (pinfunction "C_C") (pintype "passive"))
      (node (ref "LED1") (pin "4") (pinfunction "GND_4") (pintype "power_in"))
      (node (ref "LED2") (pin "4") (pinfunction "GND_4") (pintype "power_in"))
      (node (ref "LED3") (pin "4") (pinfunction "GND_4") (pintype "power_in"))
      (node (ref "LED4") (pin "4") (pinfunction "GND_4") (pintype "power_in"))
      (node (ref "MS2") (pin "4") (pinfunction "GND_4") (pintype "power_in"))
      (node (ref "MS2") (pin "4B") (pinfunction "GND_4B") (pintype "power_in"))
      (node (ref "NEOPIX1") (pin "1") (pinfunction "1_1") (pintype "passive"))
      (node (ref "Q4") (pin "2") (pinfunction "S_2") (pintype "bidirectional"))
      (node (ref "R14") (pin "2") (pinfunction "2_2") (pintype "passive"))
      (node (ref "R15") (pin "6") (pinfunction "2_6") (pintype "passive"))
      (node (ref "R15") (pin "7") (pinfunction "2_7") (pintype "passive"))
      (node (ref "R25") (pin "2") (pinfunction "2_2") (pintype "passive"))
      (node (ref "R3") (pin "1") (pinfunction "1_1") (pintype "passive"))
      (node (ref "SENSE1") (pin "1") (pinfunction "1_1") (pintype "passive"))
      (node (ref "SW1") (pin "O2") (pinfunction "O2_O2") (pintype "passive"))
      (node (ref "SW3") (pin "B") (pinfunction "S_B") (pintype "passive"))
      (node (ref "SW3") (pin "B'") (pinfunction "S1_B'") (pintype "passive"))
      (node (ref "TFT1") (pin "21") (pinfunction "GND_21") (pintype "power_in"))
      (node (ref "TFT1") (pin "22") (pinfunction "GND_22") (pintype "power_in"))
      (node (ref "TFT1") (pin "8") (pinfunction "GND_8") (pintype "power_in"))
      (node (ref "U$63") (pin "22") (pinfunction "GND_1_22") (pintype "bidirectional"))
      (node (ref "U$63") (pin "33") (pinfunction "GND_2_33") (pintype "bidirectional"))
      (node (ref "U$63") (pin "47") (pinfunction "GND_3_47") (pintype "bidirectional"))
      (node (ref "U$63") (pin "54") (pinfunction "GND_4_54") (pintype "bidirectional"))
      (node (ref "U$63") (pin "7") (pinfunction "GND_0_7") (pintype "bidirectional"))
      (node (ref "U$63") (pin "EXP") (pinfunction "GND_0_EXP") (pintype "bidirectional"))
      (node (ref "U6") (pin "2") (pinfunction "GND_2") (pintype "power_in"))
      (node (ref "U7") (pin "2") (pinfunction "VSS_2") (pintype "power_in"))
      (node (ref "U9") (pin "4") (pinfunction "VSS_4") (pintype "bidirectional"))
      (node (ref "X2") (pin "BASE@1") (pinfunction "GND_BASE@1") (pintype "power_in"))
      (node (ref "X2") (pin "BASE@2") (pinfunction "GND_BASE@2") (pintype "power_in"))
      (node (ref "X2") (pin "GND") (pinfunction "GND_GND") (pintype "power_in"))
      (node (ref "X2") (pin "SPRT@1") (pinfunction "GND_SPRT@1") (pintype "power_in"))
      (node (ref "X2") (pin "SPRT@2") (pinfunction "GND_SPRT@2") (pintype "power_in"))
      (node (ref "X2") (pin "SPRT@3") (pinfunction "GND_SPRT@3") (pintype "power_in"))
      (node (ref "X2") (pin "SPRT@4") (pinfunction "GND_SPRT@4") (pintype "power_in"))
      (node (ref "X4") (pin "1") (pinfunction "1_1") (pintype "passive"))
    )
    (net (code "56") (name "Net-(C31-Pad2)") (class "Default")
      (node (ref "C31") (pin "2") (pinfunction "2_2") (pintype "passive"))
      (node (ref "R24") (pin "1") (pinfunction "1_1") (pintype "passive"))
    )
    (net (code "57") (name "Net-(CHG1-PadC)") (class "Default")
      (node (ref "CHG1") (pin "C") (pinfunction "C_C") (pintype "passive"))
      (node (ref "R11") (pin "1") (pinfunction "1_1") (pintype "passive"))
    )
    (net (code "58") (name "Net-(IC3-IN)") (class "Default")
      (node (ref "IC3") (pin "3") (pinfunction "IN_3") (pintype "input"))
      (node (ref "R24") (pin "2") (pinfunction "2_2") (pintype "passive"))
    )
    (net (code "59") (name "Net-(L1-PadA)") (class "Default")
      (node (ref "L1") (pin "A") (pinfunction "A_A") (pintype "passive"))
      (node (ref "R10") (pin "2") (pinfunction "2_2") (pintype "passive"))
    )
    (net (code "60") (name "Net-(LED1-DI)") (class "Default")
      (node (ref "LED1") (pin "1") (pinfunction "DI_1") (pintype "input"))
      (node (ref "LED2") (pin "3") (pinfunction "DO_3") (pintype "output"))
    )
    (net (code "61") (name "Net-(LED1-DO)") (class "Default")
      (node (ref "LED1") (pin "3") (pinfunction "DO_3") (pintype "output"))
      (node (ref "LED3") (pin "1") (pinfunction "DI_1") (pintype "input"))
    )
    (net (code "62") (name "Net-(LED3-DO)") (class "Default")
      (node (ref "LED3") (pin "3") (pinfunction "DO_3") (pintype "output"))
      (node (ref "LED4") (pin "1") (pinfunction "DI_1") (pintype "input"))
    )
    (net (code "63") (name "Net-(NEOPIX1-Pad3)") (class "Default")
      (node (ref "NEOPIX1") (pin "3") (pinfunction "3_3") (pintype "passive"))
      (node (ref "R17") (pin "1") (pinfunction "1_1") (pintype "passive"))
    )
    (net (code "64") (name "Net-(Q4-D)") (class "Default")
      (node (ref "Q4") (pin "3") (pinfunction "D_3") (pintype "bidirectional"))
      (node (ref "R23") (pin "2") (pinfunction "2_2") (pintype "passive"))
    )
    (net (code "65") (name "Net-(Q5-S)") (class "Default")
      (node (ref "D3") (pin "C") (pinfunction "C_C") (pintype "passive"))
      (node (ref "Q5") (pin "2") (pinfunction "S_2") (pintype "passive"))
      (node (ref "Q6") (pin "2") (pinfunction "S_2") (pintype "passive"))
      (node (ref "SW1") (pin "S2") (pinfunction "S2_S2") (pintype "passive"))
    )
    (net (code "66") (name "Net-(R18-Pad1)") (class "Default")
      (node (ref "R18") (pin "1") (pinfunction "1_1") (pintype "passive"))
      (node (ref "SENSE1") (pin "3") (pinfunction "3_3") (pintype "passive"))
    )
    (net (code "67") (name "Net-(TFT1-LEDK)") (class "Default")
      (node (ref "R23") (pin "1") (pinfunction "1_1") (pintype "passive"))
      (node (ref "TFT1") (pin "32") (pinfunction "LEDK_32") (pintype "input"))
    )
    (net (code "68") (name "Net-(U$63C-VDDCORE)") (class "Default")
      (node (ref "C26") (pin "1") (pinfunction "1_1") (pintype "passive"))
      (node (ref "C27") (pin "1") (pinfunction "1_1") (pintype "passive"))
      (node (ref "U$63") (pin "53") (pinfunction "VDDCORE_53") (pintype "bidirectional"))
    )
    (net (code "69") (name "Net-(U7-PROG)") (class "Default")
      (node (ref "R14") (pin "1") (pinfunction "1_1") (pintype "passive"))
      (node (ref "U7") (pin "5") (pinfunction "PROG_5") (pintype "input"))
    )
    (net (code "70") (name "Net-(U7-STAT)") (class "Default")
      (node (ref "R11") (pin "2") (pinfunction "2_2") (pintype "passive"))
      (node (ref "U7") (pin "1") (pinfunction "STAT_1") (pintype "output"))
    )
    (net (code "71") (name "V+") (class "Default")
      (node (ref "C21") (pin "1") (pinfunction "1_1") (pintype "passive"))
      (node (ref "C22") (pin "1") (pinfunction "1_1") (pintype "passive"))
      (node (ref "IC3") (pin "5") (pinfunction "VDD_5") (pintype "power_in"))
      (node (ref "LED1") (pin "2") (pinfunction "VDD_2") (pintype "power_in"))
      (node (ref "LED2") (pin "2") (pinfunction "VDD_2") (pintype "power_in"))
      (node (ref "LED3") (pin "2") (pinfunction "VDD_2") (pintype "power_in"))
      (node (ref "LED4") (pin "2") (pinfunction "VDD_2") (pintype "power_in"))
      (node (ref "Q6") (pin "3") (pinfunction "D_3") (pintype "passive"))
      (node (ref "R15") (pin "5") (pinfunction "2_5") (pintype "passive"))
      (node (ref "SJ2") (pin "1") (pinfunction "1_1") (pintype "passive"))
      (node (ref "U6") (pin "1") (pinfunction "IN_1") (pintype "power_in"))
    )
    (net (code "72") (name "VBAT") (class "Default")
      (node (ref "C17") (pin "1") (pinfunction "1_1") (pintype "passive"))
      (node (ref "MS2") (pin "28") (pinfunction "VBAT_28") (pintype "power_in"))
      (node (ref "MS2") (pin "28B") (pinfunction "VBAT_28B") (pintype "power_in"))
      (node (ref "Q5") (pin "3") (pinfunction "D_3") (pintype "passive"))
      (node (ref "R15") (pin "8") (pinfunction "2_8") (pintype "passive"))
      (node (ref "U7") (pin "3") (pinfunction "VBAT_3") (pintype "power_in"))
      (node (ref "X4") (pin "2") (pinfunction "2_2") (pintype "passive"))
    )
    (net (code "73") (name "VBUS") (class "Default")
      (node (ref "CHG1") (pin "A") (pinfunction "A_A") (pintype "passive"))
      (node (ref "D3") (pin "A") (pinfunction "A_A") (pintype "passive"))
      (node (ref "MS2") (pin "26") (pinfunction "USB_26") (pintype "power_in"))
      (node (ref "MS2") (pin "26B") (pinfunction "USB_26B") (pintype "power_in"))
      (node (ref "Q5") (pin "1") (pinfunction "G_1") (pintype "passive"))
      (node (ref "R15") (pin "3") (pinfunction "1_3") (pintype "passive"))
      (node (ref "U7") (pin "4") (pinfunction "VDD_4") (pintype "power_in"))
      (node (ref "X2") (pin "VBUS") (pinfunction "VBUS_VBUS") (pintype "power_in"))
    )
    (net (code "74") (name "VCC") (class "Default")
      (node (ref "C19") (pin "1") (pinfunction "1_1") (pintype "passive"))
      (node (ref "I2C1") (pin "2") (pinfunction "V+_2") (pintype "passive"))
      (node (ref "NEOPIX1") (pin "2") (pinfunction "2_2") (pintype "passive"))
      (node (ref "R27") (pin "1") (pinfunction "1_1") (pintype "passive"))
      (node (ref "R27") (pin "4") (pinfunction "1_4") (pintype "passive"))
      (node (ref "SENSE1") (pin "2") (pinfunction "2_2") (pintype "passive"))
      (node (ref "SJ2") (pin "2") (pinfunction "2_2") (pintype "passive"))
    )
    (net (code "75") (name "unconnected-(LED4-DO-Pad3)") (class "Default")
      (node (ref "LED4") (pin "3") (pinfunction "DO_3") (pintype "output"))
    )
    (net (code "76") (name "unconnected-(SW1-PadO1)") (class "Default")
      (node (ref "SW1") (pin "O1") (pinfunction "O1_O1") (pintype "passive"))
    )
    (net (code "77") (name "unconnected-(SW1-PadP1)") (class "Default")
      (node (ref "SW1") (pin "P1") (pinfunction "P1_P1") (pintype "passive"))
    )
    (net (code "78") (name "unconnected-(SW1-PadS1)") (class "Default")
      (node (ref "SW1") (pin "S1") (pinfunction "S1_S1") (pintype "passive"))
    )
    (net (code "79") (name "unconnected-(U$63B-PB00{slash}I0{slash}AIN12{slash}SERCOM5.2-Pad61)") (class "Default")
      (node (ref "U$63") (pin "61") (pinfunction "PB00/I0/AIN12/SERCOM5.2_61") (pintype "bidirectional"))
    )
    (net (code "80") (name "unconnected-(U$63B-PB06{slash}I6{slash}AIN8-Pad9)") (class "Default")
      (node (ref "U$63") (pin "9") (pinfunction "PB06/I6/AIN8_9") (pintype "bidirectional"))
    )
    (net (code "81") (name "unconnected-(U$63B-PB07{slash}I7{slash}AIN9-Pad10)") (class "Default")
      (node (ref "U$63") (pin "10") (pinfunction "PB07/I7/AIN9_10") (pintype "bidirectional"))
    )
    (net (code "82") (name "unconnected-(U$63B-PB17{slash}SERCOM5.1{slash}I2SMCK0-Pad40)") (class "Default")
      (node (ref "U$63") (pin "40") (pinfunction "PB17/SERCOM5.1/I2SMCK0_40") (pintype "bidirectional"))
    )
    (net (code "83") (name "unconnected-(U$63C-VSW-Pad55)") (class "Default")
      (node (ref "U$63") (pin "55") (pinfunction "VSW_55") (pintype "bidirectional"))
    )
    (net (code "84") (name "unconnected-(U6-P4-Pad4)") (class "Default")
      (node (ref "U6") (pin "4") (pinfunction "P4_4") (pintype "bidirectional"))
    )
  )
)
